# Moteino-Door-Shield.net
KiCad netlist of a schematic drawn in EAGLE
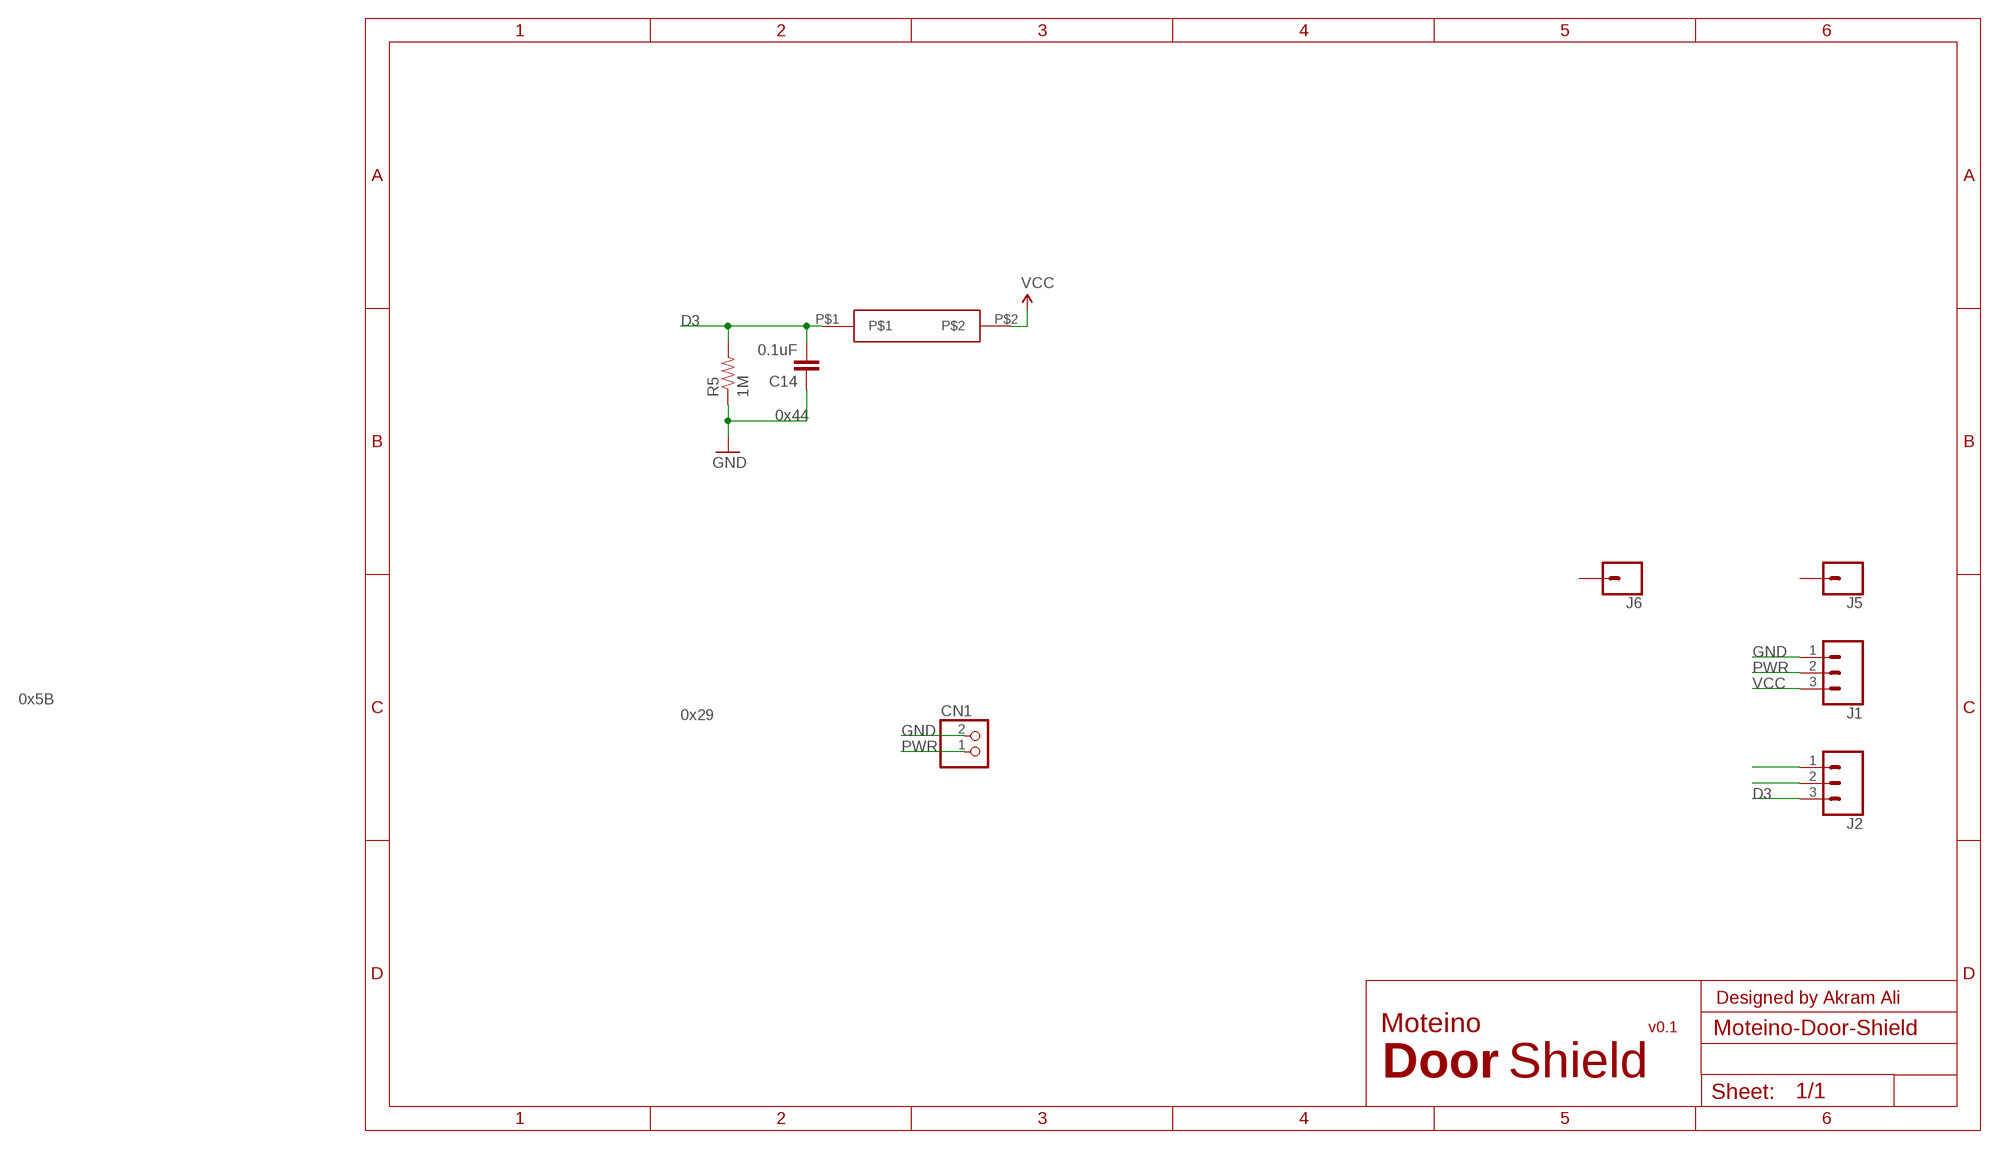
[diagram p0: schematic, sheet 1]

(export (version "E")
  (design (tool "Eeschema 10.0.6"))
  (components
    (comp (ref "C14")
      (value "0.1uF")
      (footprint "eagle-import:0805")
      (fields (field (name "MPN") "CC0805KRX7R9BB104"))
      (libsource (lib "eagle-import") (part "CAP0805"))
    )
    (comp (ref "CN1")
      (value "JST_2PIN-SMT-RA")
      (footprint "eagle-import:JST-PH-2-SMT-RA")
      (libsource (lib "eagle-import") (part "JST_2PIN-SMT-RA"))
    )
    (comp (ref "J1")
      (value "CONN_03")
      (footprint "eagle-import:1X03")
      (libsource (lib "eagle-import") (part "CONN_03"))
    )
    (comp (ref "J2")
      (value "CONN_03")
      (footprint "eagle-import:1X03")
      (libsource (lib "eagle-import") (part "CONN_03"))
    )
    (comp (ref "J5")
      (value "CONN_01")
      (footprint "eagle-import:1X01")
      (libsource (lib "eagle-import") (part "CONN_01"))
    )
    (comp (ref "J6")
      (value "CONN_01")
      (footprint "eagle-import:1X01")
      (libsource (lib "eagle-import") (part "CONN_01"))
    )
    (comp (ref "R5")
      (value "1M")
      (footprint "eagle-import:0805")
      (fields (field (name "MPN") "RC0805FR-0710KL"))
      (libsource (lib "eagle-import") (part "RESISTOR0805-RES"))
    )
    (comp (ref "U$1")
      (value "SWITCH-REED-SPSPT-NO")
      (footprint "eagle-import:SMD")
      (libsource (lib "eagle-import") (part "SWITCH-REED-SPSPT-NO"))
    )
  )
  (nets
    (net (code "1") (name "/D3") (class "Default")
      (node (ref "C14") (pin "2") (pinfunction "2_2") (pintype "passive"))
      (node (ref "J2") (pin "3") (pinfunction "3_3") (pintype "passive"))
      (node (ref "R5") (pin "2") (pinfunction "2_2") (pintype "passive"))
      (node (ref "U$1") (pin "P$1") (pinfunction "P$1_P$1") (pintype "bidirectional"))
    )
    (net (code "2") (name "/PWR") (class "Default")
      (node (ref "CN1") (pin "1") (pinfunction "2_1") (pintype "passive"))
      (node (ref "J1") (pin "2") (pinfunction "2_2") (pintype "passive"))
    )
    (net (code "3") (name "GND") (class "Default")
      (node (ref "C14") (pin "1") (pinfunction "1_1") (pintype "passive"))
      (node (ref "CN1") (pin "2") (pinfunction "1_2") (pintype "passive"))
      (node (ref "J1") (pin "1") (pinfunction "1_1") (pintype "passive"))
      (node (ref "R5") (pin "1") (pinfunction "1_1") (pintype "passive"))
    )
    (net (code "4") (name "VCC") (class "Default")
      (node (ref "J1") (pin "3") (pinfunction "3_3") (pintype "passive"))
      (node (ref "U$1") (pin "P$2") (pinfunction "P$2_P$2") (pintype "bidirectional"))
    )
    (net (code "5") (name "unconnected-(J2-Pad1)") (class "Default")
      (node (ref "J2") (pin "1") (pinfunction "1_1") (pintype "passive"))
    )
    (net (code "6") (name "unconnected-(J2-Pad2)") (class "Default")
      (node (ref "J2") (pin "2") (pinfunction "2_2") (pintype "passive"))
    )
    (net (code "7") (name "unconnected-(J5-Pad1)") (class "Default")
      (node (ref "J5") (pin "1") (pinfunction "1_1") (pintype "passive"))
    )
    (net (code "8") (name "unconnected-(J6-Pad1)") (class "Default")
      (node (ref "J6") (pin "1") (pinfunction "1_1") (pintype "passive"))
    )
  )
)
